# MCU.net
KiCad netlist of a schematic drawn in Altium Designer
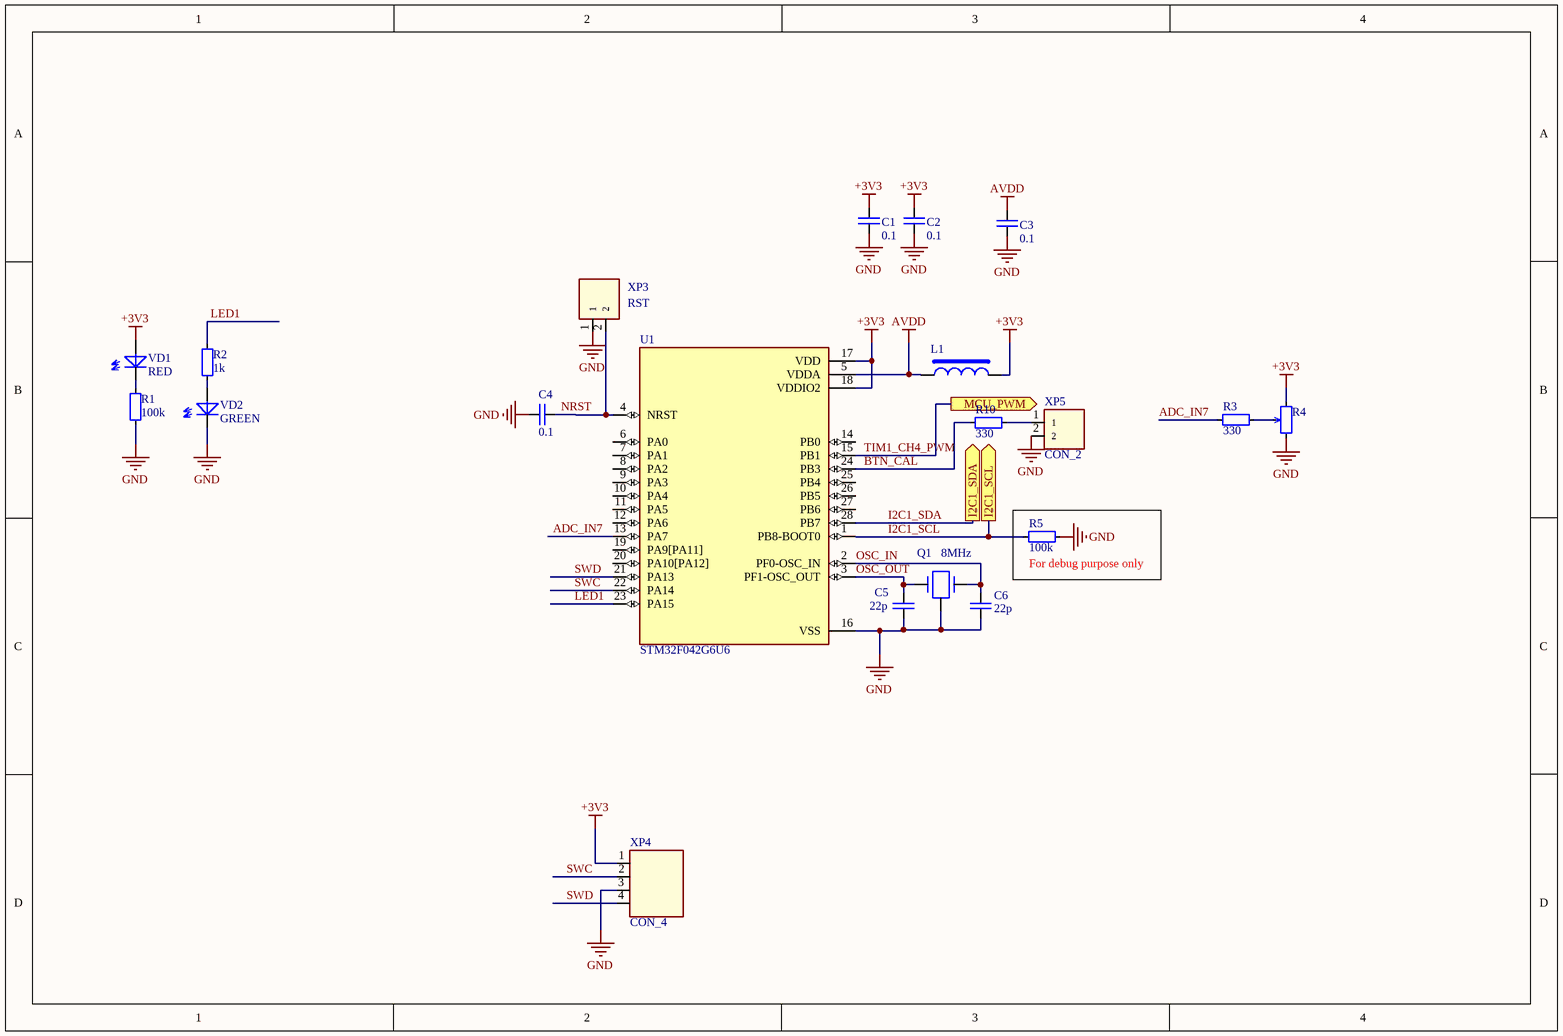
[diagram p0: MCU.SchDoc]

(export (version "E")
  (design (tool "Eeschema 10.0.6"))
  (components
    (comp (ref "C1")
      (value "0.1")
      (footprint "DISCRETE:CAP_0603")
      (description "None polar capacitor")
      (libsource (lib "DISCRETE") (part "C_NONE_POLAR"))
    )
    (comp (ref "C2")
      (value "0.1")
      (footprint "DISCRETE:CAP_0603")
      (description "None polar capacitor")
      (libsource (lib "DISCRETE") (part "C_NONE_POLAR"))
    )
    (comp (ref "C3")
      (value "0.1")
      (footprint "DISCRETE:CAP_0603")
      (description "None polar capacitor")
      (libsource (lib "DISCRETE") (part "C_NONE_POLAR"))
    )
    (comp (ref "C4")
      (value "0.1")
      (footprint "DISCRETE:CAP_0603")
      (description "None polar capacitor")
      (libsource (lib "DISCRETE") (part "C_NONE_POLAR"))
    )
    (comp (ref "C5")
      (value "22p")
      (footprint "DISCRETE:CAP_0603")
      (description "None polar capacitor")
      (libsource (lib "DISCRETE") (part "C_NONE_POLAR"))
    )
    (comp (ref "C6")
      (value "22p")
      (footprint "DISCRETE:CAP_0603")
      (description "None polar capacitor")
      (libsource (lib "DISCRETE") (part "C_NONE_POLAR"))
    )
    (comp (ref "L1")
      (value "~")
      (footprint "DISCRETE:SMD_0603")
      (description "Ferrite Bread")
      (libsource (lib "DISCRETE") (part "FB"))
    )
    (comp (ref "Q1")
      (value "8MHz")
      (footprint "DISCRETE:CSTCC-CRYSTAL")
      (description "Crystal oscillator")
      (libsource (lib "DISCRETE") (part "CRYSTAL_CAP"))
    )
    (comp (ref "R1")
      (value "100k")
      (footprint "DISCRETE:SMD_0603")
      (description "Resistor")
      (libsource (lib "") (part "RES_1"))
    )
    (comp (ref "R2")
      (value "1k")
      (footprint "DISCRETE:SMD_0603")
      (description "Resistor")
      (libsource (lib "") (part "RES_1"))
    )
    (comp (ref "R3")
      (value "330")
      (footprint "DISCRETE:SMD_0603")
      (description "Resistor")
      (libsource (lib "DISCRETE") (part "RES"))
    )
    (comp (ref "R4")
      (value "~")
      (footprint "DISCRETE:RES-ADJ-SMD-Panasonic")
      (description "Agjustable resistor")
      (libsource (lib "DISCRETE") (part "RES_ADJ"))
    )
    (comp (ref "R5")
      (value "100k")
      (footprint "DISCRETE:SMD_0603")
      (description "Resistor")
      (libsource (lib "DISCRETE") (part "RES"))
    )
    (comp (ref "R10")
      (value "330")
      (footprint "DISCRETE:SMD_0603")
      (description "Resistor")
      (libsource (lib "DISCRETE") (part "RES"))
    )
    (comp (ref "U1")
      (value "STM32F042G6U6")
      (footprint "ICs:UFQFPN_4x4_STM32F042G6U6")
      (description "ARM Cortex-M0 STM32F0 Microcontroller IC 32-Bit 48MHz 32KB x 8kB FLASH 28-UFQFPN _4x4_")
      (fields (field (name "MF") "STMicroelectronics"))
      (libsource (lib "ICs") (part "STM32F042G6U6"))
    )
    (comp (ref "VD1")
      (value "RED")
      (footprint "DISCRETE:LED_0603")
      (description "LED")
      (libsource (lib "DISCRETE") (part "LED"))
    )
    (comp (ref "VD2")
      (value "GREEN")
      (footprint "DISCRETE:LED_0603")
      (description "LED")
      (libsource (lib "DISCRETE") (part "LED"))
    )
    (comp (ref "XP3")
      (value "RST")
      (footprint "Connectors:HEAD_MICRO_SF_1.27-2")
      (libsource (lib "") (part "CON_2_1"))
    )
    (comp (ref "XP4")
      (value "CON_4")
      (footprint "Connectors:HEAD-1/4/2.54")
      (libsource (lib "Connectors") (part "CON_4"))
    )
    (comp (ref "XP5")
      (value "CON_2")
      (footprint "Connectors:HEAD_MICRO_SF_1.27-2")
      (libsource (lib "Connectors") (part "CON_2"))
    )
  )
  (nets
    (net (code "1") (name "+3V3") (class "Default")
      (node (ref "C1") (pin "1") (pintype "passive"))
      (node (ref "C2") (pin "1") (pintype "passive"))
      (node (ref "L1") (pin "2") (pinfunction "2_2") (pintype "passive"))
      (node (ref "R4") (pin "2") (pintype "passive"))
      (node (ref "U1") (pin "17") (pinfunction "VDD_17") (pintype "power_in"))
      (node (ref "U1") (pin "18") (pinfunction "VDDIO2_18") (pintype "power_in"))
      (node (ref "VD1") (pin "2") (pinfunction "A_2") (pintype "passive"))
      (node (ref "XP4") (pin "1") (pinfunction "1_1") (pintype "passive"))
    )
    (net (code "2") (name "/ADC_IN7") (class "Default")
      (node (ref "R3") (pin "2") (pintype "passive"))
      (node (ref "U1") (pin "13") (pinfunction "PA7_13") (pintype "bidirectional"))
    )
    (net (code "3") (name "/BTN_CAL") (class "Default")
      (node (ref "R10") (pin "2") (pintype "passive"))
      (node (ref "U1") (pin "24") (pinfunction "PB3_24") (pintype "bidirectional"))
    )
    (net (code "4") (name "/I2C1_SCL") (class "Default")
      (node (ref "R5") (pin "2") (pintype "passive"))
      (node (ref "U1") (pin "1") (pinfunction "PB8-BOOT0_1") (pintype "bidirectional"))
    )
    (net (code "5") (name "/I2C1_SDA") (class "Default")
      (node (ref "U1") (pin "28") (pinfunction "PB7_28") (pintype "bidirectional"))
    )
    (net (code "6") (name "/LED1") (class "Default")
      (node (ref "R2") (pin "1") (pintype "passive"))
      (node (ref "U1") (pin "23") (pinfunction "PA15_23") (pintype "bidirectional"))
    )
    (net (code "7") (name "/NRST") (class "Default")
      (node (ref "C4") (pin "2") (pintype "passive"))
      (node (ref "U1") (pin "4") (pinfunction "NRST_4") (pintype "bidirectional"))
      (node (ref "XP3") (pin "2") (pinfunction "2_2") (pintype "passive"))
    )
    (net (code "8") (name "/OSC_IN") (class "Default")
      (node (ref "C6") (pin "1") (pintype "passive"))
      (node (ref "Q1") (pin "1") (pinfunction "1_1") (pintype "passive"))
      (node (ref "U1") (pin "2") (pinfunction "PF0-OSC_IN_2") (pintype "bidirectional"))
    )
    (net (code "9") (name "/OSC_OUT") (class "Default")
      (node (ref "C5") (pin "1") (pintype "passive"))
      (node (ref "Q1") (pin "3") (pinfunction "3_3") (pintype "passive"))
      (node (ref "U1") (pin "3") (pinfunction "PF1-OSC_OUT_3") (pintype "bidirectional"))
    )
    (net (code "10") (name "/SWC") (class "Default")
      (node (ref "U1") (pin "22") (pinfunction "PA14_22") (pintype "bidirectional"))
      (node (ref "XP4") (pin "2") (pinfunction "2_2") (pintype "passive"))
    )
    (net (code "11") (name "/SWD") (class "Default")
      (node (ref "U1") (pin "21") (pinfunction "PA13_21") (pintype "bidirectional"))
      (node (ref "XP4") (pin "4") (pinfunction "4_4") (pintype "passive"))
    )
    (net (code "12") (name "/TIM1_CH4_PWM") (class "Default")
      (node (ref "U1") (pin "15") (pinfunction "PB1_15") (pintype "bidirectional"))
    )
    (net (code "13") (name "AVDD") (class "Default")
      (node (ref "C3") (pin "1") (pintype "passive"))
      (node (ref "L1") (pin "1") (pinfunction "1_1") (pintype "passive"))
      (node (ref "U1") (pin "5") (pinfunction "VDDA_5") (pintype "power_in"))
    )
    (net (code "14") (name "GND") (class "Default")
      (node (ref "C1") (pin "2") (pintype "passive"))
      (node (ref "C2") (pin "2") (pintype "passive"))
      (node (ref "C3") (pin "2") (pintype "passive"))
      (node (ref "C4") (pin "1") (pintype "passive"))
      (node (ref "C5") (pin "2") (pintype "passive"))
      (node (ref "C6") (pin "2") (pintype "passive"))
      (node (ref "Q1") (pin "2") (pinfunction "2_2") (pintype "passive"))
      (node (ref "R1") (pin "2") (pintype "passive"))
      (node (ref "R4") (pin "1") (pintype "passive"))
      (node (ref "R5") (pin "1") (pintype "passive"))
      (node (ref "U1") (pin "16") (pinfunction "VSS_16") (pintype "power_in"))
      (node (ref "VD2") (pin "1") (pinfunction "C_1") (pintype "passive"))
      (node (ref "XP3") (pin "1") (pinfunction "1_1") (pintype "passive"))
      (node (ref "XP4") (pin "3") (pinfunction "3_3") (pintype "passive"))
      (node (ref "XP5") (pin "2") (pinfunction "2_2") (pintype "passive"))
    )
    (net (code "15") (name "Net-(R3-Pad1)") (class "Default")
      (node (ref "R3") (pin "1") (pintype "passive"))
      (node (ref "R4") (pin "3") (pintype "passive"))
    )
    (net (code "16") (name "Net-(R10-Pad1)") (class "Default")
      (node (ref "R10") (pin "1") (pintype "passive"))
      (node (ref "XP5") (pin "1") (pinfunction "1_1") (pintype "passive"))
    )
    (net (code "17") (name "Net-(VD1-C)") (class "Default")
      (node (ref "R1") (pin "1") (pintype "passive"))
      (node (ref "VD1") (pin "1") (pinfunction "C_1") (pintype "passive"))
    )
    (net (code "18") (name "Net-(VD2-A)") (class "Default")
      (node (ref "R2") (pin "2") (pintype "passive"))
      (node (ref "VD2") (pin "2") (pinfunction "A_2") (pintype "passive"))
    )
    (net (code "19") (name "unconnected-(U1-PA0-Pad6)") (class "Default")
      (node (ref "U1") (pin "6") (pinfunction "PA0_6") (pintype "bidirectional"))
    )
    (net (code "20") (name "unconnected-(U1-PA1-Pad7)") (class "Default")
      (node (ref "U1") (pin "7") (pinfunction "PA1_7") (pintype "bidirectional"))
    )
    (net (code "21") (name "unconnected-(U1-PA2-Pad8)") (class "Default")
      (node (ref "U1") (pin "8") (pinfunction "PA2_8") (pintype "bidirectional"))
    )
    (net (code "22") (name "unconnected-(U1-PA3-Pad9)") (class "Default")
      (node (ref "U1") (pin "9") (pinfunction "PA3_9") (pintype "bidirectional"))
    )
    (net (code "23") (name "unconnected-(U1-PA4-Pad10)") (class "Default")
      (node (ref "U1") (pin "10") (pinfunction "PA4_10") (pintype "bidirectional"))
    )
    (net (code "24") (name "unconnected-(U1-PA5-Pad11)") (class "Default")
      (node (ref "U1") (pin "11") (pinfunction "PA5_11") (pintype "bidirectional"))
    )
    (net (code "25") (name "unconnected-(U1-PA6-Pad12)") (class "Default")
      (node (ref "U1") (pin "12") (pinfunction "PA6_12") (pintype "bidirectional"))
    )
    (net (code "26") (name "unconnected-(U1-PA9[PA11]-Pad19)") (class "Default")
      (node (ref "U1") (pin "19") (pinfunction "PA9[PA11]_19") (pintype "bidirectional"))
    )
    (net (code "27") (name "unconnected-(U1-PA10[PA12]-Pad20)") (class "Default")
      (node (ref "U1") (pin "20") (pinfunction "PA10[PA12]_20") (pintype "bidirectional"))
    )
    (net (code "28") (name "unconnected-(U1-PB0-Pad14)") (class "Default")
      (node (ref "U1") (pin "14") (pinfunction "PB0_14") (pintype "bidirectional"))
    )
    (net (code "29") (name "unconnected-(U1-PB4-Pad25)") (class "Default")
      (node (ref "U1") (pin "25") (pinfunction "PB4_25") (pintype "bidirectional"))
    )
    (net (code "30") (name "unconnected-(U1-PB5-Pad26)") (class "Default")
      (node (ref "U1") (pin "26") (pinfunction "PB5_26") (pintype "bidirectional"))
    )
    (net (code "31") (name "unconnected-(U1-PB6-Pad27)") (class "Default")
      (node (ref "U1") (pin "27") (pinfunction "PB6_27") (pintype "bidirectional"))
    )
  )
)
